# Sensors.net
KiCad netlist of a schematic drawn in Altium Designer
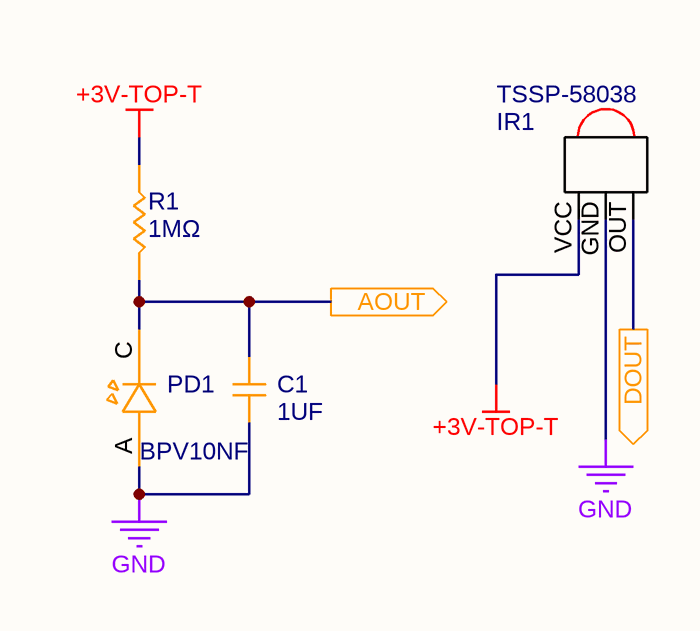
[diagram p0: Sensors.SchDoc]

(export (version "E")
  (design (tool "Eeschema 10.0.6"))
  (components
    (comp (ref "C1")
      (value "1UF")
      (footprint "CAP_0603")
      (description "Capacitor SMD 0603 generic")
      (libsource (lib "RC") (part "CAP_0603"))
    )
    (comp (ref "IR1")
      (value "TSSP-58038")
      (footprint "TSSP-58038")
      (libsource (lib "RC") (part "TSSP-58038"))
    )
    (comp (ref "PD1") (value "BPV10NF") (footprint "BPV10NF") (libsource (lib "RC") (part "BPV10NF")))
    (comp (ref "R1")
      (value "1MΩ")
      (footprint "RES_0603")
      (description "Resistor SMD 0603 generic")
      (libsource (lib "RC") (part "RES_0603"))
    )
  )
  (nets
    (net (code "1") (name "+3V-TOP-T") (class "Default")
      (node (ref "IR1") (pin "VCC") (pintype "passive"))
      (node (ref "R1") (pin "2") (pintype "passive"))
    )
    (net (code "2") (name "/AOUT") (class "Default")
      (node (ref "C1") (pin "1") (pintype "passive"))
      (node (ref "PD1") (pin "C") (pinfunction "C_C") (pintype "passive"))
      (node (ref "R1") (pin "1") (pintype "passive"))
    )
    (net (code "3") (name "/DOUT") (class "Default") (node (ref "IR1") (pin "OUT") (pintype "passive")))
    (net (code "4") (name "GND") (class "Default")
      (node (ref "C1") (pin "2") (pintype "passive"))
      (node (ref "IR1") (pin "GND") (pintype "passive"))
      (node (ref "PD1") (pin "A") (pinfunction "A_A") (pintype "passive"))
    )
  )
)
